# CAN-to-CAN.net
KiCad netlist of a schematic drawn in Altium Designer
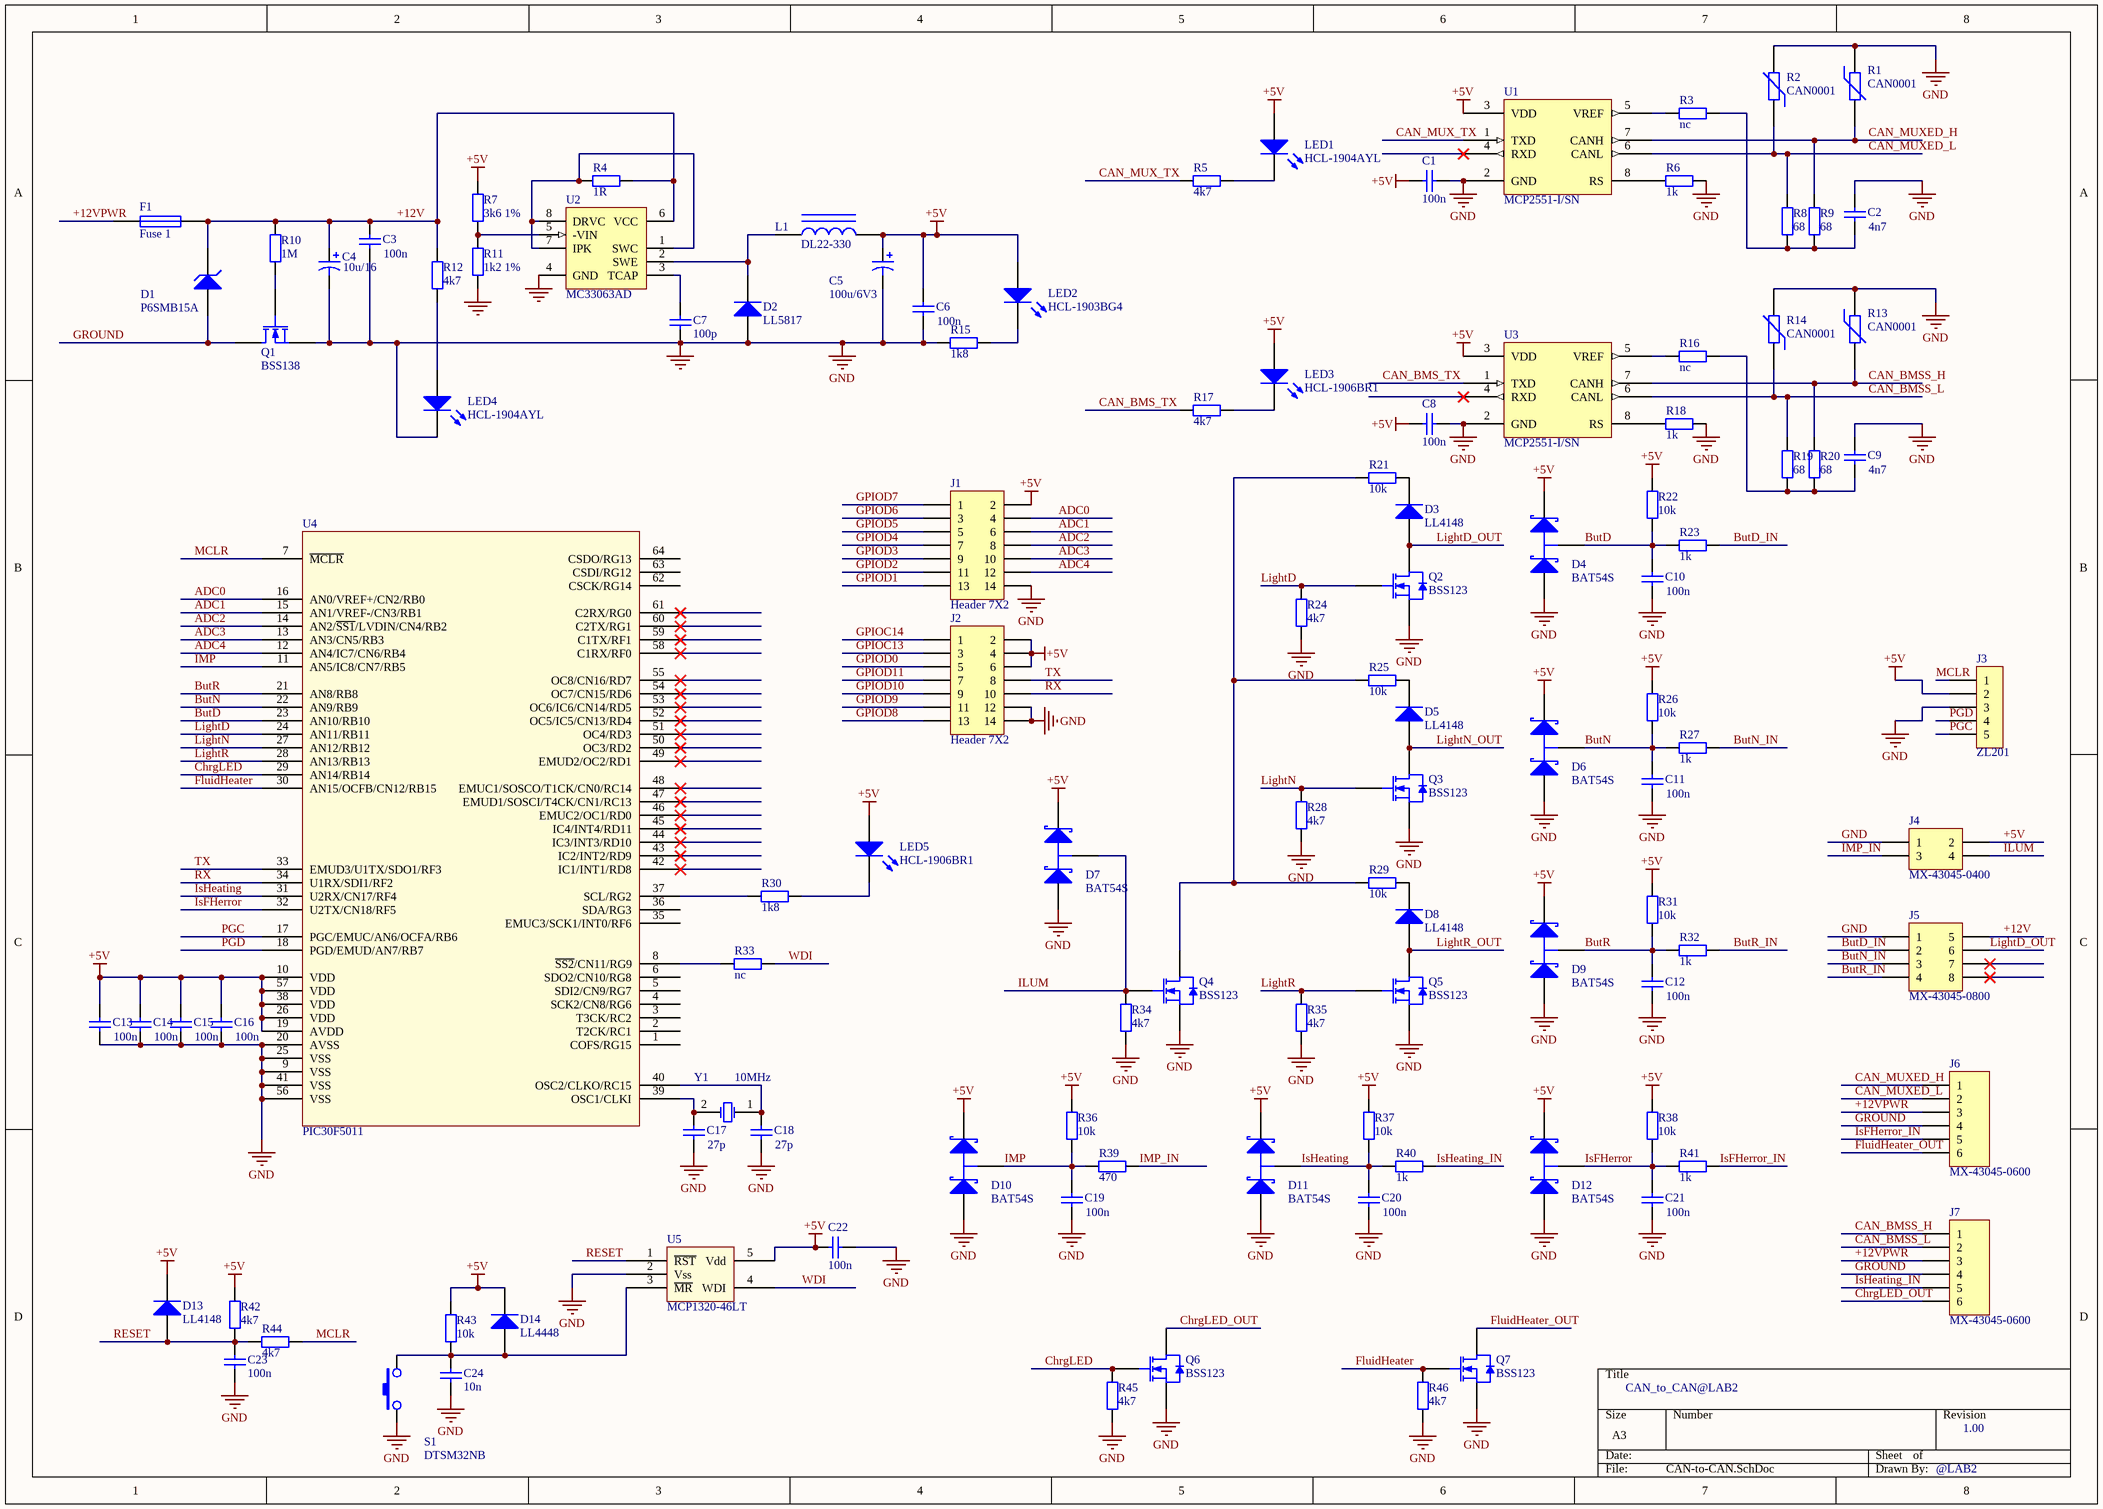
[diagram p0: CAN-to-CAN.SchDoc]

(export (version "E")
  (design (tool "Eeschema 10.0.6"))
  (components
    (comp (ref "C1")
      (value "100n")
      (footprint "0603")
      (description "Capacitor")
      (libsource (lib "Miscellaneous Devices") (part "Cap"))
    )
    (comp (ref "C2")
      (value "4n7")
      (footprint "0603")
      (description "Capacitor")
      (libsource (lib "Miscellaneous Devices") (part "Cap"))
    )
    (comp (ref "C3")
      (value "100n")
      (footprint "MHDR2X4")
      (description "Capacitor")
      (libsource (lib "Miscellaneous Devices") (part "Cap"))
    )
    (comp (ref "C4")
      (value "10u/16")
      (footprint "SMB_V-RJ45")
      (description "Polarized Capacitor (Radial)")
      (libsource (lib "Miscellaneous Devices") (part "Cap Pol1"))
    )
    (comp (ref "C5")
      (value "100u/6V3")
      (footprint "SMB_V-RJ45")
      (description "Polarized Capacitor (Radial)")
      (libsource (lib "Miscellaneous Devices") (part "Cap Pol1"))
    )
    (comp (ref "C6")
      (value "100n")
      (footprint "0603")
      (description "Capacitor")
      (libsource (lib "Miscellaneous Devices") (part "Cap"))
    )
    (comp (ref "C7")
      (value "100p")
      (footprint "0603")
      (description "Capacitor")
      (libsource (lib "Miscellaneous Devices") (part "Cap"))
    )
    (comp (ref "C8")
      (value "100n")
      (footprint "0603")
      (description "Capacitor")
      (libsource (lib "Miscellaneous Devices") (part "Cap"))
    )
    (comp (ref "C9")
      (value "4n7")
      (footprint "0603")
      (description "Capacitor")
      (libsource (lib "Miscellaneous Devices") (part "Cap"))
    )
    (comp (ref "C10")
      (value "100n")
      (footprint "0603")
      (description "Capacitor")
      (libsource (lib "Miscellaneous Devices") (part "Cap"))
    )
    (comp (ref "C11")
      (value "100n")
      (footprint "0603")
      (description "Capacitor")
      (libsource (lib "Miscellaneous Devices") (part "Cap"))
    )
    (comp (ref "C12")
      (value "100n")
      (footprint "0603")
      (description "Capacitor")
      (libsource (lib "Miscellaneous Devices") (part "Cap"))
    )
    (comp (ref "C13")
      (value "100n")
      (footprint "0603")
      (description "Capacitor")
      (libsource (lib "Miscellaneous Devices") (part "Cap"))
    )
    (comp (ref "C14")
      (value "100n")
      (footprint "0603")
      (description "Capacitor")
      (libsource (lib "Miscellaneous Devices") (part "Cap"))
    )
    (comp (ref "C15")
      (value "100n")
      (footprint "0603")
      (description "Capacitor")
      (libsource (lib "Miscellaneous Devices") (part "Cap"))
    )
    (comp (ref "C16")
      (value "100n")
      (footprint "0603")
      (description "Capacitor")
      (libsource (lib "Miscellaneous Devices") (part "Cap"))
    )
    (comp (ref "C17")
      (value "27p")
      (footprint "0603")
      (description "Capacitor")
      (libsource (lib "Miscellaneous Devices") (part "Cap"))
    )
    (comp (ref "C18")
      (value "27p")
      (footprint "0603")
      (description "Capacitor")
      (libsource (lib "Miscellaneous Devices") (part "Cap"))
    )
    (comp (ref "C19")
      (value "100n")
      (footprint "0603")
      (description "Capacitor")
      (libsource (lib "Miscellaneous Devices") (part "Cap"))
    )
    (comp (ref "C20")
      (value "100n")
      (footprint "0603")
      (description "Capacitor")
      (libsource (lib "Miscellaneous Devices") (part "Cap"))
    )
    (comp (ref "C21")
      (value "100n")
      (footprint "0603")
      (description "Capacitor")
      (libsource (lib "Miscellaneous Devices") (part "Cap"))
    )
    (comp (ref "C22")
      (value "100n")
      (footprint "0603")
      (description "Capacitor")
      (libsource (lib "Miscellaneous Devices") (part "Cap"))
    )
    (comp (ref "C23")
      (value "100n")
      (footprint "0603")
      (description "Capacitor")
      (libsource (lib "Miscellaneous Devices") (part "Cap"))
    )
    (comp (ref "C24")
      (value "10n")
      (footprint "0603")
      (description "Capacitor")
      (libsource (lib "Miscellaneous Devices") (part "Cap"))
    )
    (comp (ref "D1")
      (value "P6SMB15A")
      (footprint "SMB")
      (description "Zener Diode")
      (libsource (lib "Miscellaneous Devices") (part "D Zener"))
    )
    (comp (ref "D2")
      (value "LL5817")
      (footprint "SMB_V-RJ45")
      (description "High Conductance Fast Diode")
      (libsource (lib "FSC Discrete Diode") (part "1N4148"))
    )
    (comp (ref "D3")
      (value "LL4148")
      (footprint "RCA/4.5-H2")
      (description "High Conductance Fast Diode")
      (libsource (lib "FSC Discrete Diode") (part "1N4148"))
    )
    (comp (ref "D4")
      (value "BAT54S")
      (footprint "RCA/4.5-H2")
      (description "Schottky Barrier Double Diode")
      (libsource (lib "Philips Discrete Diode - Schottky") (part "BAT54S"))
    )
    (comp (ref "D5")
      (value "LL4148")
      (footprint "RCA/4.5-H2")
      (description "High Conductance Fast Diode")
      (libsource (lib "FSC Discrete Diode") (part "1N4148"))
    )
    (comp (ref "D6")
      (value "BAT54S")
      (footprint "RCA/4.5-H2")
      (description "Schottky Barrier Double Diode")
      (libsource (lib "Philips Discrete Diode - Schottky") (part "BAT54S"))
    )
    (comp (ref "D7")
      (value "BAT54S")
      (footprint "RCA/4.5-H2")
      (description "Schottky Barrier Double Diode")
      (libsource (lib "Philips Discrete Diode - Schottky") (part "BAT54S"))
    )
    (comp (ref "D8")
      (value "LL4148")
      (footprint "RCA/4.5-H2")
      (description "High Conductance Fast Diode")
      (libsource (lib "FSC Discrete Diode") (part "1N4148"))
    )
    (comp (ref "D9")
      (value "BAT54S")
      (footprint "RCA/4.5-H2")
      (description "Schottky Barrier Double Diode")
      (libsource (lib "Philips Discrete Diode - Schottky") (part "BAT54S"))
    )
    (comp (ref "D10")
      (value "BAT54S")
      (footprint "RCA/4.5-H2")
      (description "Schottky Barrier Double Diode")
      (libsource (lib "Philips Discrete Diode - Schottky") (part "BAT54S"))
    )
    (comp (ref "D11")
      (value "BAT54S")
      (footprint "RCA/4.5-H2")
      (description "Schottky Barrier Double Diode")
      (libsource (lib "Philips Discrete Diode - Schottky") (part "BAT54S"))
    )
    (comp (ref "D12")
      (value "BAT54S")
      (footprint "RCA/4.5-H2")
      (description "Schottky Barrier Double Diode")
      (libsource (lib "Philips Discrete Diode - Schottky") (part "BAT54S"))
    )
    (comp (ref "D13")
      (value "LL4148")
      (footprint "RCA/4.5-H2")
      (description "High Conductance Fast Diode")
      (libsource (lib "FSC Discrete Diode") (part "1N4148"))
    )
    (comp (ref "D14")
      (value "LL4448")
      (footprint "RCA/4.5-H2")
      (description "Default Diode")
      (libsource (lib "Miscellaneous Devices") (part "Diode"))
    )
    (comp (ref "F1")
      (value "Fuse 1")
      (footprint "1812")
      (description "Fuse")
      (libsource (lib "Miscellaneous Devices") (part "Fuse 1"))
    )
    (comp (ref "J1")
      (value "Header 7X2")
      (footprint "HDR2X7")
      (description "Header, 7-Pin, Dual row")
      (libsource (lib "Miscellaneous Connectors") (part "Header 7X2"))
    )
    (comp (ref "J2")
      (value "Header 7X2")
      (footprint "HDR2X7")
      (description "Header, 7-Pin, Dual row")
      (libsource (lib "Miscellaneous Connectors") (part "Header 7X2"))
    )
    (comp (ref "J3")
      (value "ZL201")
      (footprint "HDR1X5")
      (description "Connector")
      (libsource (lib "*") (part "CON5"))
    )
    (comp (ref "J4")
      (value "MX-43045-0400")
      (footprint "PS2-6PIN")
      (description "Header, 2-Pin, Dual row")
      (libsource (lib "Miscellaneous Connectors") (part "Header 2X2"))
    )
    (comp (ref "J5")
      (value "MX-43045-0800")
      (footprint "PS2-6PIN")
      (description "Header, 4-Pin, Dual row")
      (libsource (lib "Miscellaneous Connectors") (part "Header 4X2A"))
    )
    (comp (ref "J6")
      (value "MX-43045-0600")
      (footprint "PS2-6PIN")
      (description "Header, 6-Pin")
      (libsource (lib "Miscellaneous Connectors") (part "Header 6"))
    )
    (comp (ref "J7")
      (value "MX-43045-0600")
      (footprint "PS2-6PIN")
      (description "Header, 6-Pin")
      (libsource (lib "Miscellaneous Connectors") (part "Header 6"))
    )
    (comp (ref "L1")
      (value "DL22-330")
      (footprint "ST-3150-5N")
      (description "Magnetic-Core Inductor")
      (libsource (lib "Miscellaneous Devices") (part "Inductor Iron"))
    )
    (comp (ref "LED1")
      (value "HCL-1904AYL")
      (footprint "0603")
      (description "Typical BLUE SiC LED")
      (libsource (lib "Miscellaneous Devices") (part "LED3"))
    )
    (comp (ref "LED2")
      (value "HCL-1903BG4")
      (footprint "0603")
      (description "Typical BLUE SiC LED")
      (libsource (lib "Miscellaneous Devices") (part "LED3"))
    )
    (comp (ref "LED3")
      (value "HCL-1906BR1")
      (footprint "0603")
      (description "Typical BLUE SiC LED")
      (libsource (lib "Miscellaneous Devices") (part "LED3"))
    )
    (comp (ref "LED4")
      (value "HCL-1904AYL")
      (footprint "0603")
      (description "Typical BLUE SiC LED")
      (libsource (lib "Miscellaneous Devices") (part "LED3"))
    )
    (comp (ref "LED5")
      (value "HCL-1906BR1")
      (footprint "0603")
      (description "Typical BLUE SiC LED")
      (libsource (lib "Miscellaneous Devices") (part "LED3"))
    )
    (comp (ref "Q1")
      (value "BSS138")
      (footprint "PIN1")
      (description "N-Channel Enhancement Mode Vertical DMOS FET")
      (libsource (lib "Zetex Discrete MOSFET") (part "BSS138"))
    )
    (comp (ref "Q2")
      (value "BSS123")
      (footprint "PIN1")
      (description "N-channel Enhancement Mode Vertical D-MOSFET")
      (libsource (lib "Philips Discrete MOSFET - Low Power") (part "BSS123"))
    )
    (comp (ref "Q3")
      (value "BSS123")
      (footprint "PIN1")
      (description "N-channel Enhancement Mode Vertical D-MOSFET")
      (libsource (lib "Philips Discrete MOSFET - Low Power") (part "BSS123"))
    )
    (comp (ref "Q4")
      (value "BSS123")
      (footprint "PIN1")
      (description "N-channel Enhancement Mode Vertical D-MOSFET")
      (libsource (lib "Philips Discrete MOSFET - Low Power") (part "BSS123"))
    )
    (comp (ref "Q5")
      (value "BSS123")
      (footprint "PIN1")
      (description "N-channel Enhancement Mode Vertical D-MOSFET")
      (libsource (lib "Philips Discrete MOSFET - Low Power") (part "BSS123"))
    )
    (comp (ref "Q6")
      (value "BSS123")
      (footprint "PIN1")
      (description "N-channel Enhancement Mode Vertical D-MOSFET")
      (libsource (lib "Philips Discrete MOSFET - Low Power") (part "BSS123"))
    )
    (comp (ref "Q7")
      (value "BSS123")
      (footprint "PIN1")
      (description "N-channel Enhancement Mode Vertical D-MOSFET")
      (libsource (lib "Philips Discrete MOSFET - Low Power") (part "BSS123"))
    )
    (comp (ref "R1")
      (value "CAN0001")
      (footprint "0603")
      (description "Varistor (Voltage-Sensitive Resistor)")
      (libsource (lib "Miscellaneous Devices") (part "Res Varistor"))
    )
    (comp (ref "R2")
      (value "CAN0001")
      (footprint "0603")
      (description "Varistor (Voltage-Sensitive Resistor)")
      (libsource (lib "Miscellaneous Devices") (part "Res Varistor"))
    )
    (comp (ref "R3")
      (value "nc")
      (footprint "0603")
      (description "Resistor")
      (libsource (lib "Miscellaneous Devices") (part "Res2"))
    )
    (comp (ref "R4")
      (value "1R")
      (footprint "PIN1")
      (description "Resistor")
      (libsource (lib "Miscellaneous Devices") (part "Res2"))
    )
    (comp (ref "R5")
      (value "4k7")
      (footprint "0603")
      (description "Resistor")
      (libsource (lib "") (part "Res2_2"))
    )
    (comp (ref "R6")
      (value "1k")
      (footprint "0603")
      (description "Resistor")
      (libsource (lib "Miscellaneous Devices") (part "Res2"))
    )
    (comp (ref "R7")
      (value "3k6 1%")
      (footprint "0603")
      (description "Resistor")
      (libsource (lib "") (part "Res2_1"))
    )
    (comp (ref "R8")
      (value "68")
      (footprint "0603")
      (description "Resistor")
      (libsource (lib "") (part "Res2_1"))
    )
    (comp (ref "R9")
      (value "68")
      (footprint "0603")
      (description "Resistor")
      (libsource (lib "") (part "Res2_1"))
    )
    (comp (ref "R10")
      (value "1M")
      (footprint "0603")
      (description "Resistor")
      (libsource (lib "") (part "Res2_1"))
    )
    (comp (ref "R11")
      (value "1k2 1%")
      (footprint "0603")
      (description "Resistor")
      (libsource (lib "") (part "Res2_3"))
    )
    (comp (ref "R12")
      (value "4k7")
      (footprint "0603")
      (description "Resistor")
      (libsource (lib "") (part "Res2_1"))
    )
    (comp (ref "R13")
      (value "CAN0001")
      (footprint "0603")
      (description "Varistor (Voltage-Sensitive Resistor)")
      (libsource (lib "Miscellaneous Devices") (part "Res Varistor"))
    )
    (comp (ref "R14")
      (value "CAN0001")
      (footprint "0603")
      (description "Varistor (Voltage-Sensitive Resistor)")
      (libsource (lib "Miscellaneous Devices") (part "Res Varistor"))
    )
    (comp (ref "R15")
      (value "1k8")
      (footprint "0603")
      (description "Resistor")
      (libsource (lib "") (part "Res2_2"))
    )
    (comp (ref "R16")
      (value "nc")
      (footprint "0603")
      (description "Resistor")
      (libsource (lib "Miscellaneous Devices") (part "Res2"))
    )
    (comp (ref "R17")
      (value "4k7")
      (footprint "0603")
      (description "Resistor")
      (libsource (lib "") (part "Res2_2"))
    )
    (comp (ref "R18")
      (value "1k")
      (footprint "0603")
      (description "Resistor")
      (libsource (lib "Miscellaneous Devices") (part "Res2"))
    )
    (comp (ref "R19")
      (value "68")
      (footprint "0603")
      (description "Resistor")
      (libsource (lib "") (part "Res2_1"))
    )
    (comp (ref "R20")
      (value "68")
      (footprint "0603")
      (description "Resistor")
      (libsource (lib "") (part "Res2_1"))
    )
    (comp (ref "R21")
      (value "10k")
      (footprint "0603")
      (description "Resistor")
      (libsource (lib "Miscellaneous Devices") (part "Res2"))
    )
    (comp (ref "R22")
      (value "10k")
      (footprint "0603")
      (description "Resistor")
      (libsource (lib "") (part "Res2_1"))
    )
    (comp (ref "R23")
      (value "1k")
      (footprint "0603")
      (description "Resistor")
      (libsource (lib "") (part "Res2_2"))
    )
    (comp (ref "R24")
      (value "4k7")
      (footprint "0603")
      (description "Resistor")
      (libsource (lib "") (part "Res2_1"))
    )
    (comp (ref "R25")
      (value "10k")
      (footprint "0603")
      (description "Resistor")
      (libsource (lib "Miscellaneous Devices") (part "Res2"))
    )
    (comp (ref "R26")
      (value "10k")
      (footprint "0603")
      (description "Resistor")
      (libsource (lib "") (part "Res2_1"))
    )
    (comp (ref "R27")
      (value "1k")
      (footprint "0603")
      (description "Resistor")
      (libsource (lib "") (part "Res2_2"))
    )
    (comp (ref "R28")
      (value "4k7")
      (footprint "0603")
      (description "Resistor")
      (libsource (lib "") (part "Res2_1"))
    )
    (comp (ref "R29")
      (value "10k")
      (footprint "0603")
      (description "Resistor")
      (libsource (lib "Miscellaneous Devices") (part "Res2"))
    )
    (comp (ref "R30")
      (value "1k8")
      (footprint "0603")
      (description "Resistor")
      (libsource (lib "") (part "Res2_2"))
    )
    (comp (ref "R31")
      (value "10k")
      (footprint "0603")
      (description "Resistor")
      (libsource (lib "") (part "Res2_1"))
    )
    (comp (ref "R32")
      (value "1k")
      (footprint "0603")
      (description "Resistor")
      (libsource (lib "") (part "Res2_2"))
    )
    (comp (ref "R33")
      (value "nc")
      (footprint "0603")
      (description "Resistor")
      (libsource (lib "") (part "Res2_2"))
    )
    (comp (ref "R34")
      (value "4k7")
      (footprint "0603")
      (description "Resistor")
      (libsource (lib "") (part "Res2_1"))
    )
    (comp (ref "R35")
      (value "4k7")
      (footprint "0603")
      (description "Resistor")
      (libsource (lib "") (part "Res2_1"))
    )
    (comp (ref "R36")
      (value "10k")
      (footprint "0603")
      (description "Resistor")
      (libsource (lib "") (part "Res2_1"))
    )
    (comp (ref "R37")
      (value "10k")
      (footprint "0603")
      (description "Resistor")
      (libsource (lib "") (part "Res2_1"))
    )
    (comp (ref "R38")
      (value "10k")
      (footprint "0603")
      (description "Resistor")
      (libsource (lib "") (part "Res2_1"))
    )
    (comp (ref "R39")
      (value "470")
      (footprint "0603")
      (description "Resistor")
      (libsource (lib "") (part "Res2_2"))
    )
    (comp (ref "R40")
      (value "1k")
      (footprint "0603")
      (description "Resistor")
      (libsource (lib "") (part "Res2_2"))
    )
    (comp (ref "R41")
      (value "1k")
      (footprint "0603")
      (description "Resistor")
      (libsource (lib "") (part "Res2_2"))
    )
    (comp (ref "R42")
      (value "4k7")
      (footprint "0603")
      (description "Resistor")
      (libsource (lib "") (part "Res2_1"))
    )
    (comp (ref "R43")
      (value "10k")
      (footprint "0603")
      (description "Resistor")
      (libsource (lib "") (part "Res2_3"))
    )
    (comp (ref "R44")
      (value "4k7")
      (footprint "0603")
      (description "Resistor")
      (libsource (lib "") (part "Res2_2"))
    )
    (comp (ref "R45")
      (value "4k7")
      (footprint "0603")
      (description "Resistor")
      (libsource (lib "") (part "Res2_1"))
    )
    (comp (ref "R46")
      (value "4k7")
      (footprint "0603")
      (description "Resistor")
      (libsource (lib "") (part "Res2_1"))
    )
    (comp (ref "S1")
      (value "DTSM32NB")
      (footprint "PIN1")
      (description "Switch PushButton")
      (libsource (lib "*") (part "PUSHB"))
    )
    (comp (ref "U1")
      (value "MCP2551-I/SN")
      (footprint "SMB_V-RJ45")
      (description "High Speed CAN Transceiver, 8-Pin Plastic SOIC, Industrial Grade")
      (libsource (lib "Microchip Interface Line Transceiver") (part "MCP2551-I/SN"))
    )
    (comp (ref "U2")
      (value "MC33063AD")
      (footprint "SO8_N")
      (description "DC-to-DC Converter Control Circuit")
      (libsource (lib "Motorola Power Mgt DC-DC Converter") (part "MC33063AD"))
    )
    (comp (ref "U3")
      (value "MCP2551-I/SN")
      (footprint "SMB_V-RJ45")
      (description "High Speed CAN Transceiver, 8-Pin Plastic SOIC, Industrial Grade")
      (libsource (lib "Microchip Interface Line Transceiver") (part "MCP2551-I/SN"))
    )
    (comp (ref "U4")
      (value "PIC30F5011")
      (footprint "MHDR2X20")
      (description "PIC30F5011 - Up")
      (libsource (lib "X-Tro's Misc") (part "PIC30F5011"))
    )
    (comp (ref "U5")
      (value "MCP1320-46LT")
      (footprint "MHDR2X20")
      (libsource (lib "X-Tro's Misc") (part "MCP1320"))
    )
    (comp (ref "Y1")
      (value "10MHz")
      (footprint "SMB_V-RJ45")
      (description "Crystal Oscillator")
      (libsource (lib "Miscellaneous Devices") (part "XTAL"))
    )
  )
  (nets
    (net (code "1") (name "+5V") (class "Default")
      (node (ref "C1") (pin "1") (pinfunction "1_1") (pintype "passive"))
      (node (ref "C13") (pin "1") (pinfunction "1_1") (pintype "passive"))
      (node (ref "C14") (pin "1") (pinfunction "1_1") (pintype "passive"))
      (node (ref "C15") (pin "1") (pinfunction "1_1") (pintype "passive"))
      (node (ref "C16") (pin "1") (pinfunction "1_1") (pintype "passive"))
      (node (ref "C22") (pin "1") (pinfunction "1_1") (pintype "passive"))
      (node (ref "C5") (pin "1") (pinfunction "1_1") (pintype "passive"))
      (node (ref "C6") (pin "1") (pinfunction "1_1") (pintype "passive"))
      (node (ref "C8") (pin "1") (pinfunction "1_1") (pintype "passive"))
      (node (ref "D10") (pin "2") (pinfunction "K_2") (pintype "passive"))
      (node (ref "D11") (pin "2") (pinfunction "K_2") (pintype "passive"))
      (node (ref "D12") (pin "2") (pinfunction "K_2") (pintype "passive"))
      (node (ref "D13") (pin "2") (pinfunction "K_2") (pintype "passive"))
      (node (ref "D14") (pin "2") (pinfunction "K_2") (pintype "passive"))
      (node (ref "D4") (pin "2") (pinfunction "K_2") (pintype "passive"))
      (node (ref "D6") (pin "2") (pinfunction "K_2") (pintype "passive"))
      (node (ref "D7") (pin "2") (pinfunction "K_2") (pintype "passive"))
      (node (ref "D9") (pin "2") (pinfunction "K_2") (pintype "passive"))
      (node (ref "J1") (pin "2") (pinfunction "2_2") (pintype "passive"))
      (node (ref "J2") (pin "2") (pinfunction "2_2") (pintype "passive"))
      (node (ref "J2") (pin "4") (pinfunction "4_4") (pintype "passive"))
      (node (ref "J2") (pin "6") (pinfunction "6_6") (pintype "passive"))
      (node (ref "J3") (pin "2") (pinfunction "2_2") (pintype "passive"))
      (node (ref "J4") (pin "2") (pinfunction "2_2") (pintype "passive"))
      (node (ref "L1") (pin "2") (pinfunction "2_2") (pintype "passive"))
      (node (ref "LED1") (pin "1") (pinfunction "A_1") (pintype "passive"))
      (node (ref "LED2") (pin "1") (pinfunction "A_1") (pintype "passive"))
      (node (ref "LED3") (pin "1") (pinfunction "A_1") (pintype "passive"))
      (node (ref "LED5") (pin "1") (pinfunction "A_1") (pintype "passive"))
      (node (ref "R22") (pin "1") (pinfunction "1_1") (pintype "passive"))
      (node (ref "R26") (pin "1") (pinfunction "1_1") (pintype "passive"))
      (node (ref "R31") (pin "1") (pinfunction "1_1") (pintype "passive"))
      (node (ref "R36") (pin "1") (pinfunction "1_1") (pintype "passive"))
      (node (ref "R37") (pin "1") (pinfunction "1_1") (pintype "passive"))
      (node (ref "R38") (pin "1") (pinfunction "1_1") (pintype "passive"))
      (node (ref "R42") (pin "1") (pinfunction "1_1") (pintype "passive"))
      (node (ref "R43") (pin "2") (pinfunction "2_2") (pintype "passive"))
      (node (ref "R7") (pin "1") (pinfunction "1_1") (pintype "passive"))
      (node (ref "U1") (pin "3") (pinfunction "VDD_3") (pintype "power_in"))
      (node (ref "U3") (pin "3") (pinfunction "VDD_3") (pintype "power_in"))
      (node (ref "U4") (pin "10") (pinfunction "VDD_10") (pintype "passive"))
      (node (ref "U4") (pin "19") (pinfunction "AVDD_19") (pintype "passive"))
      (node (ref "U4") (pin "26") (pinfunction "VDD_26") (pintype "passive"))
      (node (ref "U4") (pin "38") (pinfunction "VDD_38") (pintype "passive"))
      (node (ref "U4") (pin "57") (pinfunction "VDD_57") (pintype "passive"))
      (node (ref "U5") (pin "5") (pinfunction "Vdd_5") (pintype "passive"))
    )
    (net (code "2") (name "/+12V") (class "Default")
      (node (ref "C3") (pin "1") (pinfunction "1_1") (pintype "passive"))
      (node (ref "C4") (pin "1") (pinfunction "1_1") (pintype "passive"))
      (node (ref "D1") (pin "2") (pinfunction "K_2") (pintype "passive"))
      (node (ref "F1") (pin "2") (pinfunction "2_2") (pintype "passive"))
      (node (ref "J5") (pin "5") (pinfunction "5_5") (pintype "passive"))
      (node (ref "R10") (pin "1") (pinfunction "1_1") (pintype "passive"))
      (node (ref "R12") (pin "1") (pinfunction "1_1") (pintype "passive"))
      (node (ref "R4") (pin "2") (pinfunction "2_2") (pintype "passive"))
      (node (ref "U2") (pin "6") (pinfunction "VCC_6") (pintype "power_in"))
    )
    (net (code "3") (name "/+12VPWR") (class "Default")
      (node (ref "F1") (pin "1") (pinfunction "1_1") (pintype "passive"))
      (node (ref "J6") (pin "3") (pinfunction "3_3") (pintype "passive"))
      (node (ref "J7") (pin "3") (pinfunction "3_3") (pintype "passive"))
    )
    (net (code "4") (name "/ADC0") (class "Default")
      (node (ref "J1") (pin "4") (pinfunction "4_4") (pintype "passive"))
      (node (ref "U4") (pin "16") (pinfunction "AN0/VREF+/CN2/RB0_16") (pintype "passive"))
    )
    (net (code "5") (name "/ADC1") (class "Default")
      (node (ref "J1") (pin "6") (pinfunction "6_6") (pintype "passive"))
      (node (ref "U4") (pin "15") (pinfunction "AN1/VREF-/CN3/RB1_15") (pintype "passive"))
    )
    (net (code "6") (name "/ADC2") (class "Default")
      (node (ref "J1") (pin "8") (pinfunction "8_8") (pintype "passive"))
      (node (ref "U4") (pin "14") (pinfunction "AN2/~{SS1}/LVDIN/CN4/RB2_14") (pintype "passive"))
    )
    (net (code "7") (name "/ADC3") (class "Default")
      (node (ref "J1") (pin "10") (pinfunction "10_10") (pintype "passive"))
      (node (ref "U4") (pin "13") (pinfunction "AN3/CN5/RB3_13") (pintype "passive"))
    )
    (net (code "8") (name "/ADC4") (class "Default")
      (node (ref "J1") (pin "12") (pinfunction "12_12") (pintype "passive"))
      (node (ref "U4") (pin "12") (pinfunction "AN4/IC7/CN6/RB4_12") (pintype "passive"))
    )
    (net (code "9") (name "/ButD") (class "Default")
      (node (ref "C10") (pin "1") (pinfunction "1_1") (pintype "passive"))
      (node (ref "D4") (pin "3") (pinfunction "C_3") (pintype "passive"))
      (node (ref "R22") (pin "2") (pinfunction "2_2") (pintype "passive"))
      (node (ref "R23") (pin "2") (pinfunction "2_2") (pintype "passive"))
      (node (ref "U4") (pin "23") (pinfunction "AN10/RB10_23") (pintype "passive"))
    )
    (net (code "10") (name "/ButD_IN") (class "Default")
      (node (ref "J5") (pin "2") (pinfunction "2_2") (pintype "passive"))
      (node (ref "R23") (pin "1") (pinfunction "1_1") (pintype "passive"))
    )
    (net (code "11") (name "/ButN") (class "Default")
      (node (ref "C11") (pin "1") (pinfunction "1_1") (pintype "passive"))
      (node (ref "D6") (pin "3") (pinfunction "C_3") (pintype "passive"))
      (node (ref "R26") (pin "2") (pinfunction "2_2") (pintype "passive"))
      (node (ref "R27") (pin "2") (pinfunction "2_2") (pintype "passive"))
      (node (ref "U4") (pin "22") (pinfunction "AN9/RB9_22") (pintype "passive"))
    )
    (net (code "12") (name "/ButN_IN") (class "Default")
      (node (ref "J5") (pin "3") (pinfunction "3_3") (pintype "passive"))
      (node (ref "R27") (pin "1") (pinfunction "1_1") (pintype "passive"))
    )
    (net (code "13") (name "/ButR") (class "Default")
      (node (ref "C12") (pin "1") (pinfunction "1_1") (pintype "passive"))
      (node (ref "D9") (pin "3") (pinfunction "C_3") (pintype "passive"))
      (node (ref "R31") (pin "2") (pinfunction "2_2") (pintype "passive"))
      (node (ref "R32") (pin "2") (pinfunction "2_2") (pintype "passive"))
      (node (ref "U4") (pin "21") (pinfunction "AN8/RB8_21") (pintype "passive"))
    )
    (net (code "14") (name "/ButR_IN") (class "Default")
      (node (ref "J5") (pin "4") (pinfunction "4_4") (pintype "passive"))
      (node (ref "R32") (pin "1") (pinfunction "1_1") (pintype "passive"))
    )
    (net (code "15") (name "/CAN_BMSS_H") (class "Default")
      (node (ref "J7") (pin "1") (pinfunction "1_1") (pintype "passive"))
      (node (ref "R13") (pin "2") (pinfunction "2_2") (pintype "passive"))
      (node (ref "R20") (pin "1") (pinfunction "1_1") (pintype "passive"))
      (node (ref "U3") (pin "7") (pinfunction "CANH_7") (pintype "output"))
    )
    (net (code "16") (name "/CAN_BMSS_L") (class "Default")
      (node (ref "J7") (pin "2") (pinfunction "2_2") (pintype "passive"))
      (node (ref "R14") (pin "1") (pinfunction "1_1") (pintype "passive"))
      (node (ref "R19") (pin "1") (pinfunction "1_1") (pintype "passive"))
      (node (ref "U3") (pin "6") (pinfunction "CANL_6") (pintype "output"))
    )
    (net (code "17") (name "/CAN_BMS_TX") (class "Default")
      (node (ref "R17") (pin "2") (pinfunction "2_2") (pintype "passive"))
      (node (ref "U3") (pin "1") (pinfunction "TXD_1") (pintype "input"))
    )
    (net (code "18") (name "/CAN_MUXED_H") (class "Default")
      (node (ref "J6") (pin "1") (pinfunction "1_1") (pintype "passive"))
      (node (ref "R1") (pin "2") (pinfunction "2_2") (pintype "passive"))
      (node (ref "R9") (pin "1") (pinfunction "1_1") (pintype "passive"))
      (node (ref "U1") (pin "7") (pinfunction "CANH_7") (pintype "output"))
    )
    (net (code "19") (name "/CAN_MUXED_L") (class "Default")
      (node (ref "J6") (pin "2") (pinfunction "2_2") (pintype "passive"))
      (node (ref "R2") (pin "1") (pinfunction "1_1") (pintype "passive"))
      (node (ref "R8") (pin "1") (pinfunction "1_1") (pintype "passive"))
      (node (ref "U1") (pin "6") (pinfunction "CANL_6") (pintype "output"))
    )
    (net (code "20") (name "/CAN_MUX_TX") (class "Default")
      (node (ref "R5") (pin "2") (pinfunction "2_2") (pintype "passive"))
      (node (ref "U1") (pin "1") (pinfunction "TXD_1") (pintype "input"))
    )
    (net (code "21") (name "/ChrgLED") (class "Default")
      (node (ref "Q6") (pin "3") (pinfunction "G_3") (pintype "passive"))
      (node (ref "R45") (pin "1") (pinfunction "1_1") (pintype "passive"))
      (node (ref "U4") (pin "29") (pinfunction "AN14/RB14_29") (pintype "passive"))
    )
    (net (code "22") (name "/ChrgLED_OUT") (class "Default")
      (node (ref "J7") (pin "6") (pinfunction "6_6") (pintype "passive"))
      (node (ref "Q6") (pin "1") (pinfunction "D_1") (pintype "passive"))
    )
    (net (code "23") (name "/FluidHeater") (class "Default")
      (node (ref "Q7") (pin "3") (pinfunction "G_3") (pintype "passive"))
      (node (ref "R46") (pin "1") (pinfunction "1_1") (pintype "passive"))
      (node (ref "U4") (pin "30") (pinfunction "AN15/OCFB/CN12/RB15_30") (pintype "passive"))
    )
    (net (code "24") (name "/FluidHeater_OUT") (class "Default")
      (node (ref "J6") (pin "6") (pinfunction "6_6") (pintype "passive"))
      (node (ref "Q7") (pin "1") (pinfunction "D_1") (pintype "passive"))
    )
    (net (code "25") (name "/GPIOC13") (class "Default")
      (node (ref "J2") (pin "3") (pinfunction "3_3") (pintype "passive"))
    )
    (net (code "26") (name "/GPIOC14") (class "Default")
      (node (ref "J2") (pin "1") (pinfunction "1_1") (pintype "passive"))
    )
    (net (code "27") (name "/GPIOD0") (class "Default")
      (node (ref "J2") (pin "5") (pinfunction "5_5") (pintype "passive"))
    )
    (net (code "28") (name "/GPIOD1") (class "Default")
      (node (ref "J1") (pin "13") (pinfunction "13_13") (pintype "passive"))
    )
    (net (code "29") (name "/GPIOD2") (class "Default")
      (node (ref "J1") (pin "11") (pinfunction "11_11") (pintype "passive"))
    )
    (net (code "30") (name "/GPIOD3") (class "Default")
      (node (ref "J1") (pin "9") (pinfunction "9_9") (pintype "passive"))
    )
    (net (code "31") (name "/GPIOD4") (class "Default")
      (node (ref "J1") (pin "7") (pinfunction "7_7") (pintype "passive"))
    )
    (net (code "32") (name "/GPIOD5") (class "Default")
      (node (ref "J1") (pin "5") (pinfunction "5_5") (pintype "passive"))
    )
    (net (code "33") (name "/GPIOD6") (class "Default")
      (node (ref "J1") (pin "3") (pinfunction "3_3") (pintype "passive"))
    )
    (net (code "34") (name "/GPIOD7") (class "Default")
      (node (ref "J1") (pin "1") (pinfunction "1_1") (pintype "passive"))
    )
    (net (code "35") (name "/GPIOD8") (class "Default")
      (node (ref "J2") (pin "13") (pinfunction "13_13") (pintype "passive"))
    )
    (net (code "36") (name "/GPIOD9") (class "Default")
      (node (ref "J2") (pin "11") (pinfunction "11_11") (pintype "passive"))
    )
    (net (code "37") (name "/GPIOD10") (class "Default")
      (node (ref "J2") (pin "9") (pinfunction "9_9") (pintype "passive"))
    )
    (net (code "38") (name "/GPIOD11") (class "Default")
      (node (ref "J2") (pin "7") (pinfunction "7_7") (pintype "passive"))
    )
    (net (code "39") (name "/GROUND") (class "Default")
      (node (ref "D1") (pin "1") (pinfunction "A_1") (pintype "passive"))
      (node (ref "J6") (pin "4") (pinfunction "4_4") (pintype "passive"))
      (node (ref "J7") (pin "4") (pinfunction "4_4") (pintype "passive"))
      (node (ref "Q1") (pin "1") (pinfunction "D_1") (pintype "passive"))
    )
    (net (code "40") (name "/ILUM") (class "Default")
      (node (ref "D7") (pin "3") (pinfunction "C_3") (pintype "passive"))
      (node (ref "J4") (pin "4") (pinfunction "4_4") (pintype "passive"))
      (node (ref "Q4") (pin "3") (pinfunction "G_3") (pintype "passive"))
      (node (ref "R34") (pin "1") (pinfunction "1_1") (pintype "passive"))
    )
    (net (code "41") (name "/IMP") (class "Default")
      (node (ref "C19") (pin "1") (pinfunction "1_1") (pintype "passive"))
      (node (ref "D10") (pin "3") (pinfunction "C_3") (pintype "passive"))
      (node (ref "R36") (pin "2") (pinfunction "2_2") (pintype "passive"))
      (node (ref "R39") (pin "2") (pinfunction "2_2") (pintype "passive"))
      (node (ref "U4") (pin "11") (pinfunction "AN5/IC8/CN7/RB5_11") (pintype "passive"))
    )
    (net (code "42") (name "/IMP_IN") (class "Default")
      (node (ref "J4") (pin "3") (pinfunction "3_3") (pintype "passive"))
      (node (ref "R39") (pin "1") (pinfunction "1_1") (pintype "passive"))
    )
    (net (code "43") (name "/IsFHerror") (class "Default")
      (node (ref "C21") (pin "1") (pinfunction "1_1") (pintype "passive"))
      (node (ref "D12") (pin "3") (pinfunction "C_3") (pintype "passive"))
      (node (ref "R38") (pin "2") (pinfunction "2_2") (pintype "passive"))
      (node (ref "R41") (pin "2") (pinfunction "2_2") (pintype "passive"))
      (node (ref "U4") (pin "32") (pinfunction "U2TX/CN18/RF5_32") (pintype "passive"))
    )
    (net (code "44") (name "/IsFHerror_IN") (class "Default")
      (node (ref "J6") (pin "5") (pinfunction "5_5") (pintype "passive"))
      (node (ref "R41") (pin "1") (pinfunction "1_1") (pintype "passive"))
    )
    (net (code "45") (name "/IsHeating") (class "Default")
      (node (ref "C20") (pin "1") (pinfunction "1_1") (pintype "passive"))
      (node (ref "D11") (pin "3") (pinfunction "C_3") (pintype "passive"))
      (node (ref "R37") (pin "2") (pinfunction "2_2") (pintype "passive"))
      (node (ref "R40") (pin "2") (pinfunction "2_2") (pintype "passive"))
      (node (ref "U4") (pin "31") (pinfunction "U2RX/CN17/RF4_31") (pintype "passive"))
    )
    (net (code "46") (name "/IsHeating_IN") (class "Default")
      (node (ref "J7") (pin "5") (pinfunction "5_5") (pintype "passive"))
      (node (ref "R40") (pin "1") (pinfunction "1_1") (pintype "passive"))
    )
    (net (code "47") (name "/LightD") (class "Default")
      (node (ref "Q2") (pin "3") (pinfunction "G_3") (pintype "passive"))
      (node (ref "R24") (pin "1") (pinfunction "1_1") (pintype "passive"))
      (node (ref "U4") (pin "24") (pinfunction "AN11/RB11_24") (pintype "passive"))
    )
    (net (code "48") (name "/LightD_OUT") (class "Default")
      (node (ref "D3") (pin "1") (pinfunction "A_1") (pintype "passive"))
      (node (ref "J5") (pin "6") (pinfunction "6_6") (pintype "passive"))
      (node (ref "Q2") (pin "1") (pinfunction "D_1") (pintype "passive"))
    )
    (net (code "49") (name "/LightN") (class "Default")
      (node (ref "Q3") (pin "3") (pinfunction "G_3") (pintype "passive"))
      (node (ref "R28") (pin "1") (pinfunction "1_1") (pintype "passive"))
      (node (ref "U4") (pin "27") (pinfunction "AN12/RB12_27") (pintype "passive"))
    )
    (net (code "50") (name "/LightN_OUT") (class "Default")
      (node (ref "D5") (pin "1") (pinfunction "A_1") (pintype "passive"))
      (node (ref "Q3") (pin "1") (pinfunction "D_1") (pintype "passive"))
    )
    (net (code "51") (name "/LightR") (class "Default")
      (node (ref "Q5") (pin "3") (pinfunction "G_3") (pintype "passive"))
      (node (ref "R35") (pin "1") (pinfunction "1_1") (pintype "passive"))
      (node (ref "U4") (pin "28") (pinfunction "AN13/RB13_28") (pintype "passive"))
    )
    (net (code "52") (name "/LightR_OUT") (class "Default")
      (node (ref "D8") (pin "1") (pinfunction "A_1") (pintype "passive"))
      (node (ref "Q5") (pin "1") (pinfunction "D_1") (pintype "passive"))
    )
    (net (code "53") (name "/MCLR") (class "Default")
      (node (ref "J3") (pin "1") (pinfunction "1_1") (pintype "passive"))
      (node (ref "R44") (pin "1") (pinfunction "1_1") (pintype "passive"))
      (node (ref "U4") (pin "7") (pinfunction "~{MCLR}_7") (pintype "passive"))
    )
    (net (code "54") (name "/PGC") (class "Default")
      (node (ref "J3") (pin "5") (pinfunction "5_5") (pintype "passive"))
      (node (ref "U4") (pin "17") (pinfunction "PGC/EMUC/AN6/OCFA/RB6_17") (pintype "passive"))
    )
    (net (code "55") (name "/PGD") (class "Default")
      (node (ref "J3") (pin "4") (pinfunction "4_4") (pintype "passive"))
      (node (ref "U4") (pin "18") (pinfunction "PGD/EMUD/AN7/RB7_18") (pintype "passive"))
    )
    (net (code "56") (name "/RESET") (class "Default")
      (node (ref "C23") (pin "2") (pinfunction "2_2") (pintype "passive"))
      (node (ref "D13") (pin "1") (pinfunction "A_1") (pintype "passive"))
      (node (ref "R42") (pin "2") (pinfunction "2_2") (pintype "passive"))
      (node (ref "R44") (pin "2") (pinfunction "2_2") (pintype "passive"))
      (node (ref "U5") (pin "1") (pinfunction "~{RST}_1") (pintype "passive"))
    )
    (net (code "57") (name "/RX") (class "Default")
      (node (ref "J2") (pin "10") (pinfunction "10_10") (pintype "passive"))
      (node (ref "U4") (pin "34") (pinfunction "U1RX/SDI1/RF2_34") (pintype "passive"))
    )
    (net (code "58") (name "/TX") (class "Default")
      (node (ref "J2") (pin "8") (pinfunction "8_8") (pintype "passive"))
      (node (ref "U4") (pin "33") (pinfunction "EMUD3/U1TX/SDO1/RF3_33") (pintype "passive"))
    )
    (net (code "59") (name "/WDI") (class "Default")
      (node (ref "R33") (pin "1") (pinfunction "1_1") (pintype "passive"))
      (node (ref "U5") (pin "4") (pinfunction "WDI_4") (pintype "passive"))
    )
    (net (code "60") (name "GND") (class "Default")
      (node (ref "C1") (pin "2") (pinfunction "2_2") (pintype "passive"))
      (node (ref "C10") (pin "2") (pinfunction "2_2") (pintype "passive"))
      (node (ref "C11") (pin "2") (pinfunction "2_2") (pintype "passive"))
      (node (ref "C12") (pin "2") (pinfunction "2_2") (pintype "passive"))
      (node (ref "C13") (pin "2") (pinfunction "2_2") (pintype "passive"))
      (node (ref "C14") (pin "2") (pinfunction "2_2") (pintype "passive"))
      (node (ref "C15") (pin "2") (pinfunction "2_2") (pintype "passive"))
      (node (ref "C16") (pin "2") (pinfunction "2_2") (pintype "passive"))
      (node (ref "C17") (pin "2") (pinfunction "2_2") (pintype "passive"))
      (node (ref "C18") (pin "2") (pinfunction "2_2") (pintype "passive"))
      (node (ref "C19") (pin "2") (pinfunction "2_2") (pintype "passive"))
      (node (ref "C2") (pin "1") (pinfunction "1_1") (pintype "passive"))
      (node (ref "C20") (pin "2") (pinfunction "2_2") (pintype "passive"))
      (node (ref "C21") (pin "2") (pinfunction "2_2") (pintype "passive"))
      (node (ref "C22") (pin "2") (pinfunction "2_2") (pintype "passive"))
      (node (ref "C23") (pin "1") (pinfunction "1_1") (pintype "passive"))
      (node (ref "C24") (pin "1") (pinfunction "1_1") (pintype "passive"))
      (node (ref "C3") (pin "2") (pinfunction "2_2") (pintype "passive"))
      (node (ref "C4") (pin "2") (pinfunction "2_2") (pintype "passive"))
      (node (ref "C5") (pin "2") (pinfunction "2_2") (pintype "passive"))
      (node (ref "C6") (pin "2") (pinfunction "2_2") (pintype "passive"))
      (node (ref "C7") (pin "1") (pinfunction "1_1") (pintype "passive"))
      (node (ref "C8") (pin "2") (pinfunction "2_2") (pintype "passive"))
      (node (ref "C9") (pin "1") (pinfunction "1_1") (pintype "passive"))
      (node (ref "D10") (pin "1") (pinfunction "A_1") (pintype "passive"))
      (node (ref "D11") (pin "1") (pinfunction "A_1") (pintype "passive"))
      (node (ref "D12") (pin "1") (pinfunction "A_1") (pintype "passive"))
      (node (ref "D2") (pin "1") (pinfunction "A_1") (pintype "passive"))
      (node (ref "D4") (pin "1") (pinfunction "A_1") (pintype "passive"))
      (node (ref "D6") (pin "1") (pinfunction "A_1") (pintype "passive"))
      (node (ref "D7") (pin "1") (pinfunction "A_1") (pintype "passive"))
      (node (ref "D9") (pin "1") (pinfunction "A_1") (pintype "passive"))
      (node (ref "J1") (pin "14") (pinfunction "14_14") (pintype "passive"))
      (node (ref "J2") (pin "12") (pinfunction "12_12") (pintype "passive"))
      (node (ref "J2") (pin "14") (pinfunction "14_14") (pintype "passive"))
      (node (ref "J3") (pin "3") (pinfunction "3_3") (pintype "passive"))
      (node (ref "J4") (pin "1") (pinfunction "1_1") (pintype "passive"))
      (node (ref "J5") (pin "1") (pinfunction "1_1") (pintype "passive"))
      (node (ref "LED4") (pin "2") (pinfunction "K_2") (pintype "passive"))
      (node (ref "Q1") (pin "2") (pinfunction "S_2") (pintype "passive"))
      (node (ref "Q2") (pin "2") (pinfunction "S_2") (pintype "passive"))
      (node (ref "Q3") (pin "2") (pinfunction "S_2") (pintype "passive"))
      (node (ref "Q4") (pin "2") (pinfunction "S_2") (pintype "passive"))
      (node (ref "Q5") (pin "2") (pinfunction "S_2") (pintype "passive"))
      (node (ref "Q6") (pin "2") (pinfunction "S_2") (pintype "passive"))
      (node (ref "Q7") (pin "2") (pinfunction "S_2") (pintype "passive"))
      (node (ref "R1") (pin "1") (pinfunction "1_1") (pintype "passive"))
      (node (ref "R11") (pin "1") (pinfunction "1_1") (pintype "passive"))
      (node (ref "R13") (pin "1") (pinfunction "1_1") (pintype "passive"))
      (node (ref "R14") (pin "2") (pinfunction "2_2") (pintype "passive"))
      (node (ref "R15") (pin "2") (pinfunction "2_2") (pintype "passive"))
      (node (ref "R18") (pin "2") (pinfunction "2_2") (pintype "passive"))
      (node (ref "R2") (pin "2") (pinfunction "2_2") (pintype "passive"))
      (node (ref "R24") (pin "2") (pinfunction "2_2") (pintype "passive"))
      (node (ref "R28") (pin "2") (pinfunction "2_2") (pintype "passive"))
      (node (ref "R34") (pin "2") (pinfunction "2_2") (pintype "passive"))
      (node (ref "R35") (pin "2") (pinfunction "2_2") (pintype "passive"))
      (node (ref "R45") (pin "2") (pinfunction "2_2") (pintype "passive"))
      (node (ref "R46") (pin "2") (pinfunction "2_2") (pintype "passive"))
      (node (ref "R6") (pin "2") (pinfunction "2_2") (pintype "passive"))
      (node (ref "S1") (pin "1") (pintype "passive"))
      (node (ref "U1") (pin "2") (pinfunction "GND_2") (pintype "power_in"))
      (node (ref "U2") (pin "4") (pinfunction "GND_4") (pintype "power_in"))
      (node (ref "U3") (pin "2") (pinfunction "GND_2") (pintype "power_in"))
      (node (ref "U4") (pin "20") (pinfunction "AVSS_20") (pintype "passive"))
      (node (ref "U4") (pin "25") (pinfunction "VSS_25") (pintype "passive"))
      (node (ref "U4") (pin "41") (pinfunction "VSS_41") (pintype "passive"))
      (node (ref "U4") (pin "56") (pinfunction "VSS_56") (pintype "passive"))
      (node (ref "U4") (pin "9") (pinfunction "VSS_9") (pintype "passive"))
      (node (ref "U5") (pin "2") (pinfunction "Vss_2") (pintype "passive"))
    )
    (net (code "61") (name "Net-(C2-Pad2)") (class "Default")
      (node (ref "C2") (pin "2") (pinfunction "2_2") (pintype "passive"))
      (node (ref "R3") (pin "2") (pinfunction "2_2") (pintype "passive"))
      (node (ref "R8") (pin "2") (pinfunction "2_2") (pintype "passive"))
      (node (ref "R9") (pin "2") (pinfunction "2_2") (pintype "passive"))
    )
    (net (code "62") (name "Net-(C9-Pad2)") (class "Default")
      (node (ref "C9") (pin "2") (pinfunction "2_2") (pintype "passive"))
      (node (ref "R16") (pin "2") (pinfunction "2_2") (pintype "passive"))
      (node (ref "R19") (pin "2") (pinfunction "2_2") (pintype "passive"))
      (node (ref "R20") (pin "2") (pinfunction "2_2") (pintype "passive"))
    )
    (net (code "63") (name "Net-(D2-K)") (class "Default")
      (node (ref "D2") (pin "2") (pinfunction "K_2") (pintype "passive"))
      (node (ref "L1") (pin "1") (pinfunction "1_1") (pintype "passive"))
      (node (ref "U2") (pin "2") (pinfunction "SWE_2") (pintype "open_emitter"))
    )
    (net (code "64") (name "Net-(D3-K)") (class "Default")
      (node (ref "D3") (pin "2") (pinfunction "K_2") (pintype "passive"))
      (node (ref "R21") (pin "2") (pinfunction "2_2") (pintype "passive"))
    )
    (net (code "65") (name "Net-(D5-K)") (class "Default")
      (node (ref "D5") (pin "2") (pinfunction "K_2") (pintype "passive"))
      (node (ref "R25") (pin "2") (pinfunction "2_2") (pintype "passive"))
    )
    (net (code "66") (name "Net-(D8-K)") (class "Default")
      (node (ref "D8") (pin "2") (pinfunction "K_2") (pintype "passive"))
      (node (ref "R29") (pin "2") (pinfunction "2_2") (pintype "passive"))
    )
    (net (code "67") (name "Net-(D14-A)") (class "Default")
      (node (ref "C24") (pin "2") (pinfunction "2_2") (pintype "passive"))
      (node (ref "D14") (pin "1") (pinfunction "A_1") (pintype "passive"))
      (node (ref "R43") (pin "1") (pinfunction "1_1") (pintype "passive"))
      (node (ref "S1") (pin "2") (pintype "passive"))
      (node (ref "U5") (pin "3") (pinfunction "~{MR}_3") (pintype "passive"))
    )
    (net (code "68") (name "Net-(LED1-K)") (class "Default")
      (node (ref "LED1") (pin "2") (pinfunction "K_2") (pintype "passive"))
      (node (ref "R5") (pin "1") (pinfunction "1_1") (pintype "passive"))
    )
    (net (code "69") (name "Net-(LED2-K)") (class "Default")
      (node (ref "LED2") (pin "2") (pinfunction "K_2") (pintype "passive"))
      (node (ref "R15") (pin "1") (pinfunction "1_1") (pintype "passive"))
    )
    (net (code "70") (name "Net-(LED3-K)") (class "Default")
      (node (ref "LED3") (pin "2") (pinfunction "K_2") (pintype "passive"))
      (node (ref "R17") (pin "1") (pinfunction "1_1") (pintype "passive"))
    )
    (net (code "71") (name "Net-(LED4-A)") (class "Default")
      (node (ref "LED4") (pin "1") (pinfunction "A_1") (pintype "passive"))
      (node (ref "R12") (pin "2") (pinfunction "2_2") (pintype "passive"))
    )
    (net (code "72") (name "Net-(LED5-K)") (class "Default")
      (node (ref "LED5") (pin "2") (pinfunction "K_2") (pintype "passive"))
      (node (ref "R30") (pin "1") (pinfunction "1_1") (pintype "passive"))
    )
    (net (code "73") (name "Net-(Q1-G)") (class "Default")
      (node (ref "Q1") (pin "3") (pinfunction "G_3") (pintype "passive"))
      (node (ref "R10") (pin "2") (pinfunction "2_2") (pintype "passive"))
    )
    (net (code "74") (name "Net-(Q4-D)") (class "Default")
      (node (ref "Q4") (pin "1") (pinfunction "D_1") (pintype "passive"))
      (node (ref "R21") (pin "1") (pinfunction "1_1") (pintype "passive"))
      (node (ref "R25") (pin "1") (pinfunction "1_1") (pintype "passive"))
      (node (ref "R29") (pin "1") (pinfunction "1_1") (pintype "passive"))
    )
    (net (code "75") (name "Net-(U1-RS)") (class "Default")
      (node (ref "R6") (pin "1") (pinfunction "1_1") (pintype "passive"))
      (node (ref "U1") (pin "8") (pinfunction "RS_8") (pintype "passive"))
    )
    (net (code "76") (name "Net-(U1-VREF)") (class "Default")
      (node (ref "R3") (pin "1") (pinfunction "1_1") (pintype "passive"))
      (node (ref "U1") (pin "5") (pinfunction "VREF_5") (pintype "output"))
    )
    (net (code "77") (name "Net-(U2--VIN)") (class "Default")
      (node (ref "R11") (pin "2") (pinfunction "2_2") (pintype "passive"))
      (node (ref "R7") (pin "2") (pinfunction "2_2") (pintype "passive"))
      (node (ref "U2") (pin "5") (pinfunction "-VIN_5") (pintype "input"))
    )
    (net (code "78") (name "Net-(U2-DRVC)") (class "Default")
      (node (ref "R4") (pin "1") (pinfunction "1_1") (pintype "passive"))
      (node (ref "U2") (pin "1") (pinfunction "SWC_1") (pintype "open_collector"))
      (node (ref "U2") (pin "7") (pinfunction "IPK_7") (pintype "passive"))
      (node (ref "U2") (pin "8") (pinfunction "DRVC_8") (pintype "open_collector"))
    )
    (net (code "79") (name "Net-(U2-TCAP)") (class "Default")
      (node (ref "C7") (pin "2") (pinfunction "2_2") (pintype "passive"))
      (node (ref "U2") (pin "3") (pinfunction "TCAP_3") (pintype "passive"))
    )
    (net (code "80") (name "Net-(U3-RS)") (class "Default")
      (node (ref "R18") (pin "1") (pinfunction "1_1") (pintype "passive"))
      (node (ref "U3") (pin "8") (pinfunction "RS_8") (pintype "passive"))
    )
    (net (code "81") (name "Net-(U3-VREF)") (class "Default")
      (node (ref "R16") (pin "1") (pinfunction "1_1") (pintype "passive"))
      (node (ref "U3") (pin "5") (pinfunction "VREF_5") (pintype "output"))
    )
    (net (code "82") (name "Net-(U4-OSC1{slash}CLKI)") (class "Default")
      (node (ref "C17") (pin "1") (pinfunction "1_1") (pintype "passive"))
      (node (ref "U4") (pin "39") (pinfunction "OSC1/CLKI_39") (pintype "passive"))
      (node (ref "Y1") (pin "2") (pinfunction "OSC2_2") (pintype "passive"))
    )
    (net (code "83") (name "Net-(U4-OSC2{slash}CLKO{slash}RC15)") (class "Default")
      (node (ref "C18") (pin "1") (pinfunction "1_1") (pintype "passive"))
      (node (ref "U4") (pin "40") (pinfunction "OSC2/CLKO/RC15_40") (pintype "passive"))
      (node (ref "Y1") (pin "1") (pinfunction "OSC1_1") (pintype "passive"))
    )
    (net (code "84") (name "Net-(U4-SCL{slash}RG2)") (class "Default")
      (node (ref "R30") (pin "2") (pinfunction "2_2") (pintype "passive"))
      (node (ref "U4") (pin "37") (pinfunction "SCL/RG2_37") (pintype "passive"))
    )
    (net (code "85") (name "Net-(U4-~{SS2}{slash}CN11{slash}RG9)") (class "Default")
      (node (ref "R33") (pin "2") (pinfunction "2_2") (pintype "passive"))
      (node (ref "U4") (pin "8") (pinfunction "~{SS2}/CN11/RG9_8") (pintype "passive"))
    )
    (net (code "86") (name "unconnected-(J5-Pad7)") (class "Default")
      (node (ref "J5") (pin "7") (pinfunction "7_7") (pintype "passive+no_connect"))
    )
    (net (code "87") (name "unconnected-(J5-Pad8)") (class "Default")
      (node (ref "J5") (pin "8") (pinfunction "8_8") (pintype "passive+no_connect"))
    )
    (net (code "88") (name "unconnected-(U1-RXD-Pad4)") (class "Default")
      (node (ref "U1") (pin "4") (pinfunction "RXD_4") (pintype "output+no_connect"))
    )
    (net (code "89") (name "unconnected-(U3-RXD-Pad4)") (class "Default")
      (node (ref "U3") (pin "4") (pinfunction "RXD_4") (pintype "output+no_connect"))
    )
    (net (code "90") (name "unconnected-(U4-C1RX{slash}RF0-Pad58)") (class "Default")
      (node (ref "U4") (pin "58") (pinfunction "C1RX/RF0_58") (pintype "passive+no_connect"))
    )
    (net (code "91") (name "unconnected-(U4-C1TX{slash}RF1-Pad59)") (class "Default")
      (node (ref "U4") (pin "59") (pinfunction "C1TX/RF1_59") (pintype "passive+no_connect"))
    )
    (net (code "92") (name "unconnected-(U4-C2RX{slash}RG0-Pad61)") (class "Default")
      (node (ref "U4") (pin "61") (pinfunction "C2RX/RG0_61") (pintype "passive+no_connect"))
    )
    (net (code "93") (name "unconnected-(U4-C2TX{slash}RG1-Pad60)") (class "Default")
      (node (ref "U4") (pin "60") (pinfunction "C2TX/RG1_60") (pintype "passive+no_connect"))
    )
    (net (code "94") (name "unconnected-(U4-COFS{slash}RG15-Pad1)") (class "Default")
      (node (ref "U4") (pin "1") (pinfunction "COFS/RG15_1") (pintype "passive"))
    )
    (net (code "95") (name "unconnected-(U4-CSCK{slash}RG14-Pad62)") (class "Default")
      (node (ref "U4") (pin "62") (pinfunction "CSCK/RG14_62") (pintype "passive"))
    )
    (net (code "96") (name "unconnected-(U4-CSDI{slash}RG12-Pad63)") (class "Default")
      (node (ref "U4") (pin "63") (pinfunction "CSDI/RG12_63") (pintype "passive"))
    )
    (net (code "97") (name "unconnected-(U4-CSDO{slash}RG13-Pad64)") (class "Default")
      (node (ref "U4") (pin "64") (pinfunction "CSDO/RG13_64") (pintype "passive"))
    )
    (net (code "98") (name "unconnected-(U4-EMUC1{slash}SOSCO{slash}T1CK{slash}CN0{slash}RC14-Pad48)") (class "Default")
      (node (ref "U4") (pin "48") (pinfunction "EMUC1/SOSCO/T1CK/CN0/RC14_48") (pintype "passive+no_connect"))
    )
    (net (code "99") (name "unconnected-(U4-EMUC2{slash}OC1{slash}RD0-Pad46)") (class "Default")
      (node (ref "U4") (pin "46") (pinfunction "EMUC2/OC1/RD0_46") (pintype "passive+no_connect"))
    )
    (net (code "100") (name "unconnected-(U4-EMUC3{slash}SCK1{slash}INT0{slash}RF6-Pad35)") (class "Default")
      (node (ref "U4") (pin "35") (pinfunction "EMUC3/SCK1/INT0/RF6_35") (pintype "passive"))
    )
    (net (code "101") (name "unconnected-(U4-EMUD1{slash}SOSCI{slash}T4CK{slash}CN1{slash}RC13-Pad47)") (class "Default")
      (node (ref "U4") (pin "47") (pinfunction "EMUD1/SOSCI/T4CK/CN1/RC13_47") (pintype "passive+no_connect"))
    )
    (net (code "102") (name "unconnected-(U4-EMUD2{slash}OC2{slash}RD1-Pad49)") (class "Default")
      (node (ref "U4") (pin "49") (pinfunction "EMUD2/OC2/RD1_49") (pintype "passive+no_connect"))
    )
    (net (code "103") (name "unconnected-(U4-IC1{slash}INT1{slash}RD8-Pad42)") (class "Default")
      (node (ref "U4") (pin "42") (pinfunction "IC1/INT1/RD8_42") (pintype "passive+no_connect"))
    )
    (net (code "104") (name "unconnected-(U4-IC2{slash}INT2{slash}RD9-Pad43)") (class "Default")
      (node (ref "U4") (pin "43") (pinfunction "IC2/INT2/RD9_43") (pintype "passive+no_connect"))
    )
    (net (code "105") (name "unconnected-(U4-IC3{slash}INT3{slash}RD10-Pad44)") (class "Default")
      (node (ref "U4") (pin "44") (pinfunction "IC3/INT3/RD10_44") (pintype "passive+no_connect"))
    )
    (net (code "106") (name "unconnected-(U4-IC4{slash}INT4{slash}RD11-Pad45)") (class "Default")
      (node (ref "U4") (pin "45") (pinfunction "IC4/INT4/RD11_45") (pintype "passive+no_connect"))
    )
    (net (code "107") (name "unconnected-(U4-OC3{slash}RD2-Pad50)") (class "Default")
      (node (ref "U4") (pin "50") (pinfunction "OC3/RD2_50") (pintype "passive+no_connect"))
    )
    (net (code "108") (name "unconnected-(U4-OC4{slash}RD3-Pad51)") (class "Default")
      (node (ref "U4") (pin "51") (pinfunction "OC4/RD3_51") (pintype "passive+no_connect"))
    )
    (net (code "109") (name "unconnected-(U4-OC5{slash}IC5{slash}CN13{slash}RD4-Pad52)") (class "Default")
      (node (ref "U4") (pin "52") (pinfunction "OC5/IC5/CN13/RD4_52") (pintype "passive+no_connect"))
    )
    (net (code "110") (name "unconnected-(U4-OC6{slash}IC6{slash}CN14{slash}RD5-Pad53)") (class "Default")
      (node (ref "U4") (pin "53") (pinfunction "OC6/IC6/CN14/RD5_53") (pintype "passive+no_connect"))
    )
    (net (code "111") (name "unconnected-(U4-OC7{slash}CN15{slash}RD6-Pad54)") (class "Default")
      (node (ref "U4") (pin "54") (pinfunction "OC7/CN15/RD6_54") (pintype "passive+no_connect"))
    )
    (net (code "112") (name "unconnected-(U4-OC8{slash}CN16{slash}RD7-Pad55)") (class "Default")
      (node (ref "U4") (pin "55") (pinfunction "OC8/CN16/RD7_55") (pintype "passive+no_connect"))
    )
    (net (code "113") (name "unconnected-(U4-SCK2{slash}CN8{slash}RG6-Pad4)") (class "Default")
      (node (ref "U4") (pin "4") (pinfunction "SCK2/CN8/RG6_4") (pintype "passive"))
    )
    (net (code "114") (name "unconnected-(U4-SDA{slash}RG3-Pad36)") (class "Default")
      (node (ref "U4") (pin "36") (pinfunction "SDA/RG3_36") (pintype "passive"))
    )
    (net (code "115") (name "unconnected-(U4-SDI2{slash}CN9{slash}RG7-Pad5)") (class "Default")
      (node (ref "U4") (pin "5") (pinfunction "SDI2/CN9/RG7_5") (pintype "passive"))
    )
    (net (code "116") (name "unconnected-(U4-SDO2{slash}CN10{slash}RG8-Pad6)") (class "Default")
      (node (ref "U4") (pin "6") (pinfunction "SDO2/CN10/RG8_6") (pintype "passive"))
    )
    (net (code "117") (name "unconnected-(U4-T2CK{slash}RC1-Pad2)") (class "Default")
      (node (ref "U4") (pin "2") (pinfunction "T2CK/RC1_2") (pintype "passive"))
    )
    (net (code "118") (name "unconnected-(U4-T3CK{slash}RC2-Pad3)") (class "Default")
      (node (ref "U4") (pin "3") (pinfunction "T3CK/RC2_3") (pintype "passive"))
    )
  )
)
